# design.net
KiCad netlist of a schematic drawn in Altium Designer
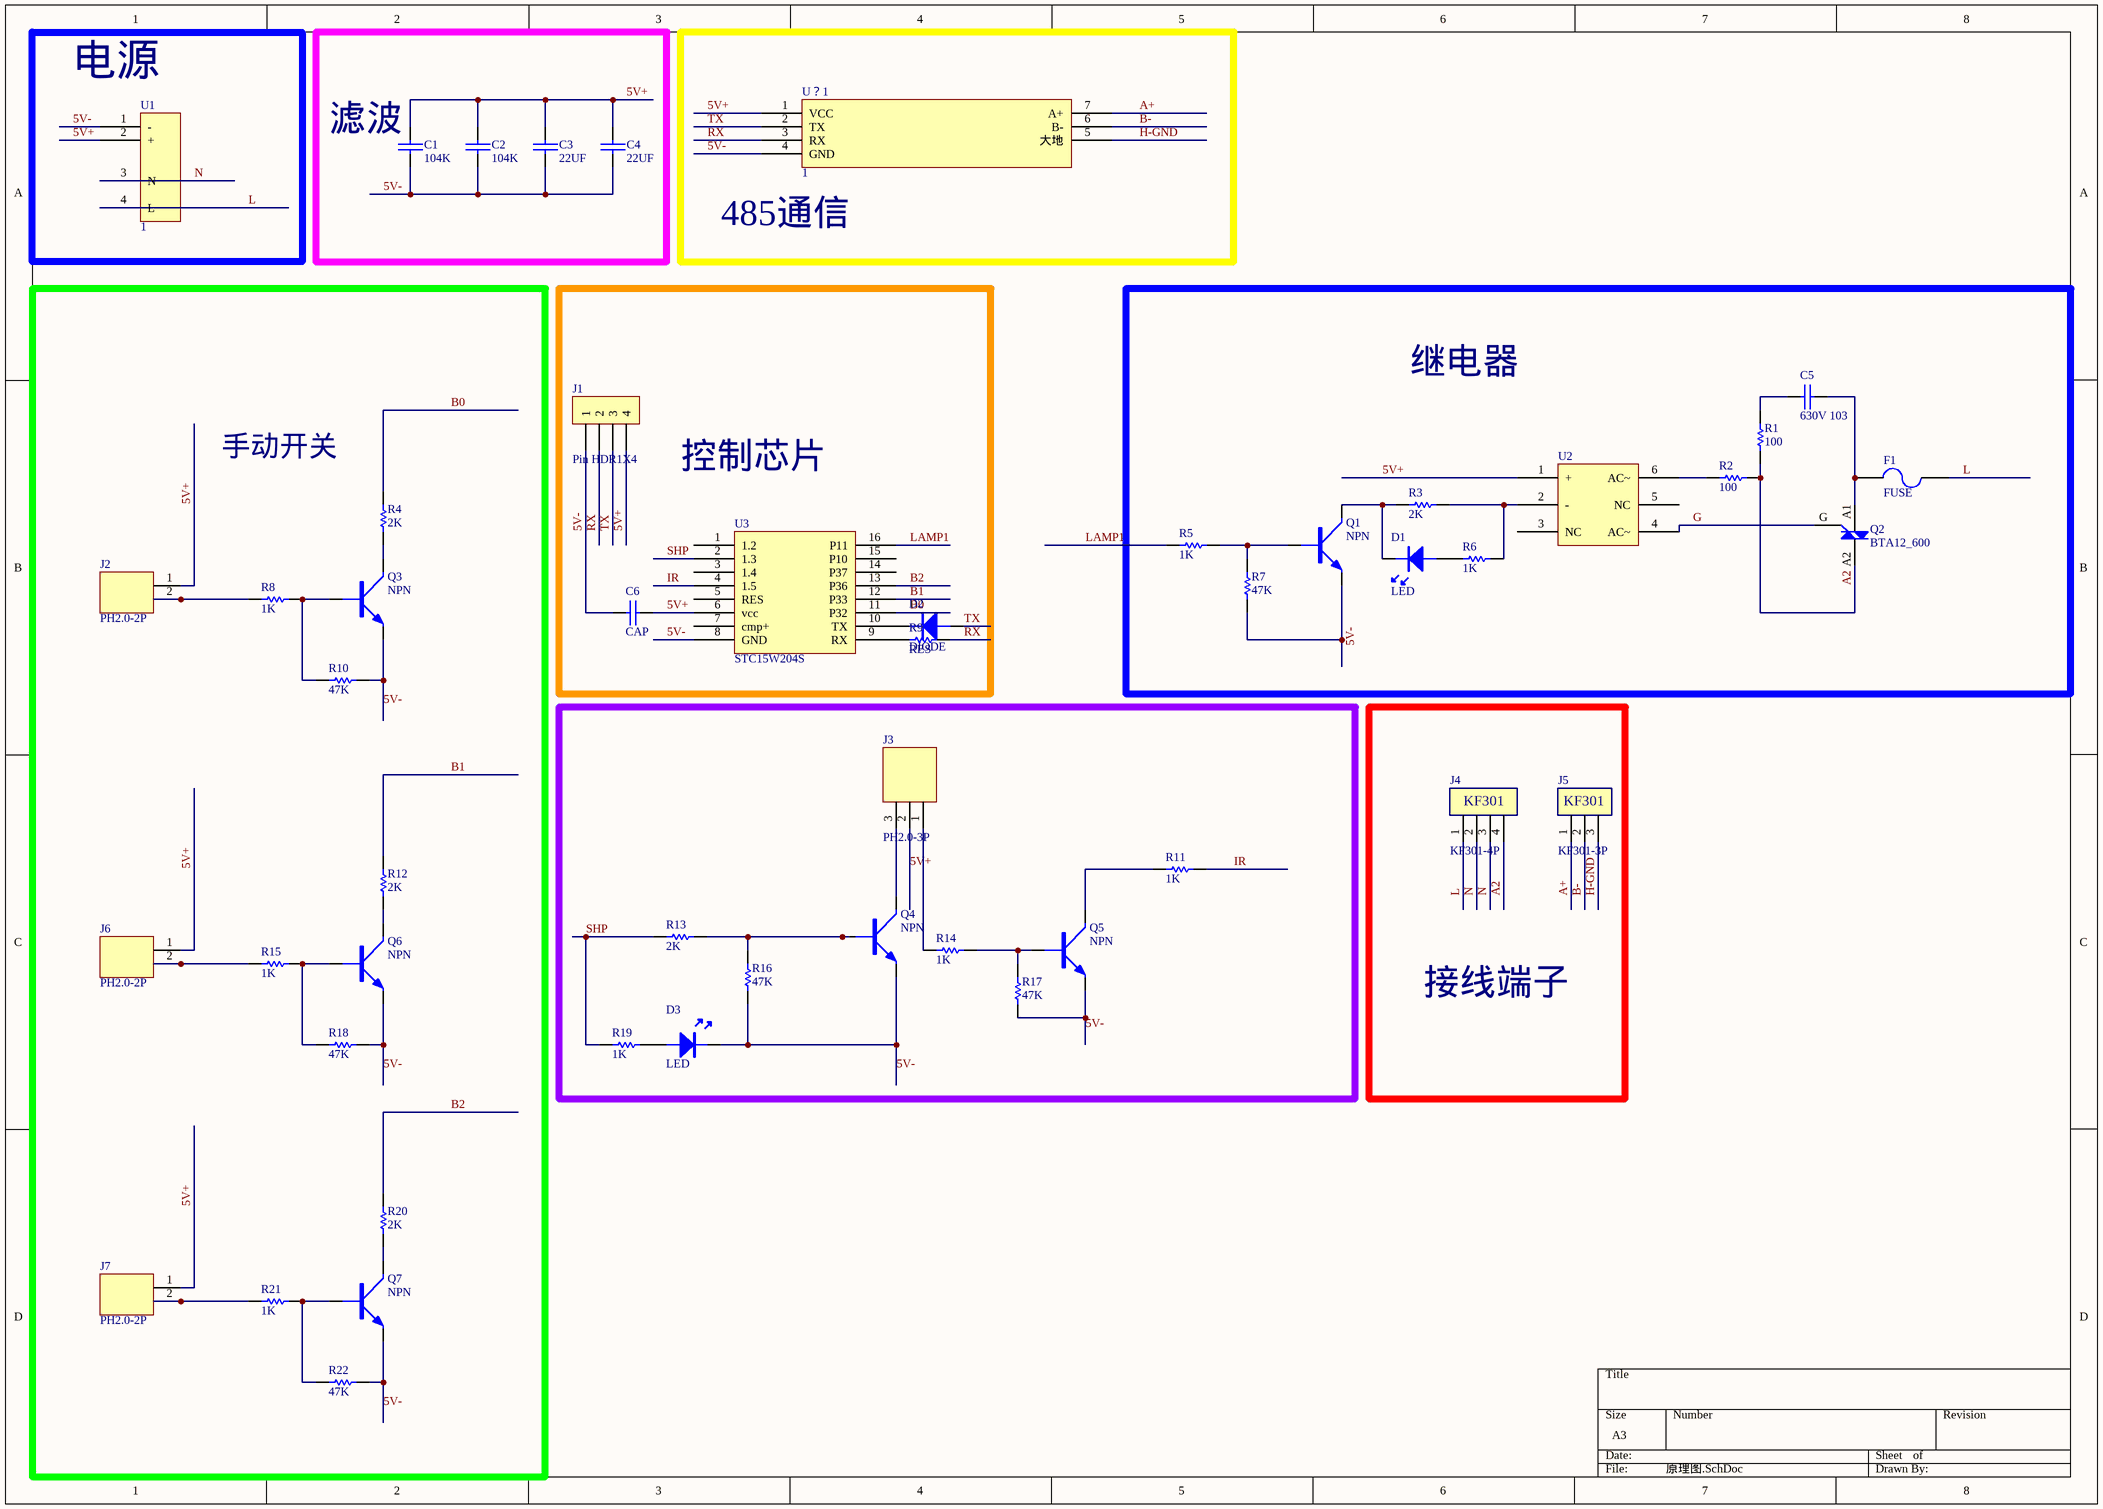
[diagram p0: 原理图.SchDoc]

(export (version "E")
  (design (tool "Eeschema 10.0.6"))
  (components
    (comp (ref "C1")
      (value "104K")
      (footprint "0603C")
      (description "无极性电容")
      (libsource (lib "电容") (part "CAP"))
    )
    (comp (ref "C2")
      (value "104K")
      (footprint "0603C")
      (description "无极性电容")
      (libsource (lib "电容") (part "CAP"))
    )
    (comp (ref "C3")
      (value "22UF")
      (footprint "0603C")
      (description "无极性电容")
      (libsource (lib "电容") (part "CAP"))
    )
    (comp (ref "C4")
      (value "22UF")
      (footprint "0603C")
      (description "无极性电容")
      (libsource (lib "电容") (part "CAP"))
    )
    (comp (ref "C5")
      (value "630V 103")
      (footprint "RAD-0.3")
      (description "无极性电容")
      (libsource (lib "电容") (part "CAP"))
    )
    (comp (ref "C6")
      (value "CAP")
      (footprint "0603C")
      (description "无极性电容")
      (libsource (lib "电容") (part "CAP"))
    )
    (comp (ref "D1") (value "LED") (footprint "LED-0603G") (libsource (lib "LED") (part "LED")))
    (comp (ref "D2")
      (value "DIODE")
      (footprint "SOD-523")
      (description "普通二极管")
      (libsource (lib "二极管") (part "DIODE"))
    )
    (comp (ref "D3") (value "LED") (footprint "LED-0603G") (libsource (lib "LED") (part "LED")))
    (comp (ref "F1") (value "FUSE") (footprint "FUSE-4x16") (libsource (lib "保险丝") (part "FUSE")))
    (comp (ref "J1") (value "Pin HDR1X4") (footprint "MHDR1X4") (libsource (lib "排针") (part "Pin HDR1X4")))
    (comp (ref "J2") (value "PH2.0-2P") (footprint "PH2.0-2P") (libsource (lib "PH") (part "PH2.0-2P")))
    (comp (ref "J3") (value "PH2.0-3P") (footprint "PH2.0-3P") (libsource (lib "PH") (part "PH2.0-3P")))
    (comp (ref "J4")
      (value "KF301-4P")
      (footprint "KF301-5.0-4P")
      (libsource (lib "KF301") (part "KF301-4P"))
    )
    (comp (ref "J5")
      (value "KF301-3P")
      (footprint "KF301-5.0-3P")
      (libsource (lib "KF301") (part "KF301-3P"))
    )
    (comp (ref "J6") (value "PH2.0-2P") (footprint "PH2.0-2P") (libsource (lib "PH") (part "PH2.0-2P")))
    (comp (ref "J7") (value "PH2.0-2P") (footprint "PH2.0-2P") (libsource (lib "PH") (part "PH2.0-2P")))
    (comp (ref "Q1")
      (value "NPN")
      (footprint "SOT-23")
      (description "NPN三极管")
      (libsource (lib "三极管") (part "NPN"))
    )
    (comp (ref "Q2")
      (value "BTA12_600")
      (footprint "TO220A")
      (description "双向可控硅")
      (libsource (lib "可控硅") (part "BTA12_600"))
    )
    (comp (ref "Q3")
      (value "NPN")
      (footprint "SOT-23")
      (description "NPN三极管")
      (libsource (lib "三极管") (part "NPN"))
    )
    (comp (ref "Q4")
      (value "NPN")
      (footprint "SOT-23")
      (description "NPN三极管")
      (libsource (lib "三极管") (part "NPN"))
    )
    (comp (ref "Q5")
      (value "NPN")
      (footprint "SOT-23")
      (description "NPN三极管")
      (libsource (lib "三极管") (part "NPN"))
    )
    (comp (ref "Q6")
      (value "NPN")
      (footprint "SOT-23")
      (description "NPN三极管")
      (libsource (lib "三极管") (part "NPN"))
    )
    (comp (ref "Q7")
      (value "NPN")
      (footprint "SOT-23")
      (description "NPN三极管")
      (libsource (lib "三极管") (part "NPN"))
    )
    (comp (ref "R1") (value "100") (footprint "AXIAL0.4") (libsource (lib "电阻") (part "RES")))
    (comp (ref "R2") (value "100") (footprint "AXIAL0.4") (libsource (lib "电阻") (part "RES")))
    (comp (ref "R3") (value "2K") (footprint "0402R") (libsource (lib "电阻") (part "RES")))
    (comp (ref "R4") (value "2K") (footprint "0402R") (libsource (lib "电阻") (part "RES")))
    (comp (ref "R5") (value "1K") (footprint "0402R") (libsource (lib "电阻") (part "RES")))
    (comp (ref "R6") (value "1K") (footprint "0402R") (libsource (lib "电阻") (part "RES")))
    (comp (ref "R7") (value "47K") (footprint "0402R") (libsource (lib "电阻") (part "RES")))
    (comp (ref "R8") (value "1K") (footprint "0402R") (libsource (lib "电阻") (part "RES")))
    (comp (ref "R9") (value "RES") (footprint "0402R") (libsource (lib "电阻") (part "RES")))
    (comp (ref "R10") (value "47K") (footprint "0402R") (libsource (lib "电阻") (part "RES")))
    (comp (ref "R11") (value "1K") (footprint "0402R") (libsource (lib "电阻") (part "RES")))
    (comp (ref "R12") (value "2K") (footprint "0402R") (libsource (lib "电阻") (part "RES")))
    (comp (ref "R13") (value "2K") (footprint "0402R") (libsource (lib "电阻") (part "RES")))
    (comp (ref "R14") (value "1K") (footprint "0402R") (libsource (lib "电阻") (part "RES")))
    (comp (ref "R15") (value "1K") (footprint "0402R") (libsource (lib "电阻") (part "RES")))
    (comp (ref "R16") (value "47K") (footprint "0402R") (libsource (lib "电阻") (part "RES")))
    (comp (ref "R17") (value "47K") (footprint "0402R") (libsource (lib "电阻") (part "RES")))
    (comp (ref "R18") (value "47K") (footprint "0402R") (libsource (lib "电阻") (part "RES")))
    (comp (ref "R19") (value "1K") (footprint "0402R") (libsource (lib "电阻") (part "RES")))
    (comp (ref "R20") (value "2K") (footprint "0402R") (libsource (lib "电阻") (part "RES")))
    (comp (ref "R21") (value "1K") (footprint "0402R") (libsource (lib "电阻") (part "RES")))
    (comp (ref "R22") (value "47K") (footprint "0402R") (libsource (lib "电阻") (part "RES")))
    (comp (ref "U1")
      (value "1")
      (footprint "开关电路")
      (libsource (lib "5v700MA_SWITCH_POWER") (part "220TO5V-power"))
    )
    (comp (ref "U2") (value "~") (footprint "DIP6") (libsource (lib "MOC3052") (part "Component_1")))
    (comp (ref "U3")
      (value "STC15W204S")
      (footprint "SOP16")
      (libsource (lib "STC15W204S") (part "STC15W204S"))
    )
    (comp (ref "U？1") (value "1") (footprint "485通信模块") (libsource (lib "485模块") (part "485通信模块")))
  )
  (nets
    (net (code "1") (name "/5V+") (class "Default")
      (node (ref "C1") (pin "2") (pinfunction "2_2") (pintype "passive"))
      (node (ref "C2") (pin "2") (pinfunction "2_2") (pintype "passive"))
      (node (ref "C3") (pin "2") (pinfunction "2_2") (pintype "passive"))
      (node (ref "C4") (pin "2") (pinfunction "2_2") (pintype "passive"))
      (node (ref "C6") (pin "2") (pinfunction "2_2") (pintype "passive"))
      (node (ref "J1") (pin "4") (pinfunction "4_4") (pintype "passive"))
      (node (ref "J2") (pin "1") (pinfunction "1_1") (pintype "passive"))
      (node (ref "J3") (pin "2") (pinfunction "2_2") (pintype "passive"))
      (node (ref "J6") (pin "1") (pinfunction "1_1") (pintype "passive"))
      (node (ref "J7") (pin "1") (pinfunction "1_1") (pintype "passive"))
      (node (ref "U1") (pin "2") (pinfunction "+_2") (pintype "passive"))
      (node (ref "U2") (pin "1") (pinfunction "+_1") (pintype "passive"))
      (node (ref "U3") (pin "6") (pinfunction "vcc_6") (pintype "passive"))
      (node (ref "U？1") (pin "1") (pinfunction "VCC_1") (pintype "passive"))
    )
    (net (code "2") (name "/5V-") (class "Default")
      (node (ref "C1") (pin "1") (pinfunction "1_1") (pintype "passive"))
      (node (ref "C2") (pin "1") (pinfunction "1_1") (pintype "passive"))
      (node (ref "C3") (pin "1") (pinfunction "1_1") (pintype "passive"))
      (node (ref "C4") (pin "1") (pinfunction "1_1") (pintype "passive"))
      (node (ref "C6") (pin "1") (pinfunction "1_1") (pintype "passive"))
      (node (ref "D3") (pin "K") (pinfunction "K_K") (pintype "passive"))
      (node (ref "J1") (pin "1") (pinfunction "1_1") (pintype "passive"))
      (node (ref "Q1") (pin "E") (pinfunction "E_E") (pintype "passive"))
      (node (ref "Q3") (pin "E") (pinfunction "E_E") (pintype "passive"))
      (node (ref "Q4") (pin "E") (pinfunction "E_E") (pintype "passive"))
      (node (ref "Q5") (pin "E") (pinfunction "E_E") (pintype "passive"))
      (node (ref "Q6") (pin "E") (pinfunction "E_E") (pintype "passive"))
      (node (ref "Q7") (pin "E") (pinfunction "E_E") (pintype "passive"))
      (node (ref "R10") (pin "2") (pinfunction "2_2") (pintype "passive"))
      (node (ref "R16") (pin "1") (pinfunction "1_1") (pintype "passive"))
      (node (ref "R17") (pin "1") (pinfunction "1_1") (pintype "passive"))
      (node (ref "R18") (pin "2") (pinfunction "2_2") (pintype "passive"))
      (node (ref "R22") (pin "2") (pinfunction "2_2") (pintype "passive"))
      (node (ref "R7") (pin "1") (pinfunction "1_1") (pintype "passive"))
      (node (ref "U1") (pin "1") (pinfunction "-_1") (pintype "passive"))
      (node (ref "U3") (pin "8") (pinfunction "GND_8") (pintype "passive"))
      (node (ref "U？1") (pin "4") (pinfunction "GND_4") (pintype "passive"))
    )
    (net (code "3") (name "/A+") (class "Default")
      (node (ref "J5") (pin "1") (pinfunction "1_1") (pintype "passive"))
      (node (ref "U？1") (pin "7") (pinfunction "A+_7") (pintype "passive"))
    )
    (net (code "4") (name "/A2") (class "Default")
      (node (ref "J4") (pin "4") (pinfunction "4_4") (pintype "passive"))
      (node (ref "Q2") (pin "A2") (pinfunction "A2_A2") (pintype "passive"))
      (node (ref "R1") (pin "1") (pinfunction "1_1") (pintype "passive"))
      (node (ref "R2") (pin "2") (pinfunction "2_2") (pintype "passive"))
    )
    (net (code "5") (name "/B-") (class "Default")
      (node (ref "J5") (pin "2") (pinfunction "2_2") (pintype "passive"))
      (node (ref "U？1") (pin "6") (pinfunction "B-_6") (pintype "passive"))
    )
    (net (code "6") (name "/B0") (class "Default")
      (node (ref "R4") (pin "2") (pinfunction "2_2") (pintype "passive"))
      (node (ref "U3") (pin "11") (pinfunction "P32_11") (pintype "passive"))
    )
    (net (code "7") (name "/B1") (class "Default")
      (node (ref "R12") (pin "2") (pinfunction "2_2") (pintype "passive"))
      (node (ref "U3") (pin "12") (pinfunction "P33_12") (pintype "passive"))
    )
    (net (code "8") (name "/B2") (class "Default")
      (node (ref "R20") (pin "2") (pinfunction "2_2") (pintype "passive"))
      (node (ref "U3") (pin "13") (pinfunction "P36_13") (pintype "passive"))
    )
    (net (code "9") (name "/G") (class "Default")
      (node (ref "Q2") (pin "G") (pinfunction "G_G") (pintype "passive"))
      (node (ref "U2") (pin "4") (pinfunction "AC~_4") (pintype "passive"))
    )
    (net (code "10") (name "/H-GND") (class "Default")
      (node (ref "J5") (pin "3") (pinfunction "3_3") (pintype "passive"))
      (node (ref "U？1") (pin "5") (pinfunction "大地_5") (pintype "passive"))
    )
    (net (code "11") (name "/IR") (class "Default")
      (node (ref "R11") (pin "2") (pinfunction "2_2") (pintype "passive"))
      (node (ref "U3") (pin "4") (pinfunction "1.5_4") (pintype "passive"))
    )
    (net (code "12") (name "/L") (class "Default")
      (node (ref "F1") (pin "2") (pinfunction "2_2") (pintype "passive"))
      (node (ref "J4") (pin "1") (pinfunction "1_1") (pintype "passive"))
      (node (ref "U1") (pin "4") (pinfunction "L_4") (pintype "passive"))
    )
    (net (code "13") (name "/LAMP1") (class "Default")
      (node (ref "R5") (pin "1") (pinfunction "1_1") (pintype "passive"))
      (node (ref "U3") (pin "16") (pinfunction "P11_16") (pintype "passive"))
    )
    (net (code "14") (name "/N") (class "Default")
      (node (ref "J4") (pin "2") (pinfunction "2_2") (pintype "passive"))
      (node (ref "J4") (pin "3") (pinfunction "3_3") (pintype "passive"))
      (node (ref "U1") (pin "3") (pinfunction "N_3") (pintype "passive"))
    )
    (net (code "15") (name "/RX") (class "Default")
      (node (ref "J1") (pin "2") (pinfunction "2_2") (pintype "passive"))
      (node (ref "R9") (pin "2") (pinfunction "2_2") (pintype "passive"))
      (node (ref "U？1") (pin "3") (pinfunction "RX_3") (pintype "passive"))
    )
    (net (code "16") (name "/SHP") (class "Default")
      (node (ref "R13") (pin "1") (pinfunction "1_1") (pintype "passive"))
      (node (ref "R19") (pin "1") (pinfunction "1_1") (pintype "passive"))
      (node (ref "U3") (pin "2") (pinfunction "1.3_2") (pintype "passive"))
    )
    (net (code "17") (name "/TX") (class "Default")
      (node (ref "D2") (pin "A") (pinfunction "A_A") (pintype "passive"))
      (node (ref "J1") (pin "3") (pinfunction "3_3") (pintype "passive"))
      (node (ref "U？1") (pin "2") (pinfunction "TX_2") (pintype "passive"))
    )
    (net (code "18") (name "Net-(C5-Pad1)") (class "Default")
      (node (ref "C5") (pin "1") (pinfunction "1_1") (pintype "passive"))
      (node (ref "R1") (pin "2") (pinfunction "2_2") (pintype "passive"))
    )
    (net (code "19") (name "Net-(C5-Pad2)") (class "Default")
      (node (ref "C5") (pin "2") (pinfunction "2_2") (pintype "passive"))
      (node (ref "F1") (pin "1") (pinfunction "1_1") (pintype "passive"))
      (node (ref "Q2") (pin "A1") (pinfunction "A1_A1") (pintype "passive"))
    )
    (net (code "20") (name "Net-(D1-PadA)") (class "Default")
      (node (ref "D1") (pin "A") (pinfunction "A_A") (pintype "passive"))
      (node (ref "R6") (pin "1") (pinfunction "1_1") (pintype "passive"))
    )
    (net (code "21") (name "Net-(D1-PadK)") (class "Default")
      (node (ref "D1") (pin "K") (pinfunction "K_K") (pintype "passive"))
      (node (ref "Q1") (pin "C") (pinfunction "C_C") (pintype "passive"))
      (node (ref "R3") (pin "1") (pinfunction "1_1") (pintype "passive"))
    )
    (net (code "22") (name "Net-(D3-PadA)") (class "Default")
      (node (ref "D3") (pin "A") (pinfunction "A_A") (pintype "passive"))
      (node (ref "R19") (pin "2") (pinfunction "2_2") (pintype "passive"))
    )
    (net (code "23") (name "Net-(J2-Pad2)") (class "Default")
      (node (ref "J2") (pin "2") (pinfunction "2_2") (pintype "passive"))
      (node (ref "R8") (pin "1") (pinfunction "1_1") (pintype "passive"))
    )
    (net (code "24") (name "Net-(J3-Pad1)") (class "Default")
      (node (ref "J3") (pin "1") (pinfunction "1_1") (pintype "passive"))
      (node (ref "R14") (pin "2") (pinfunction "2_2") (pintype "passive"))
    )
    (net (code "25") (name "Net-(J3-Pad3)") (class "Default")
      (node (ref "J3") (pin "3") (pinfunction "3_3") (pintype "passive"))
      (node (ref "Q4") (pin "C") (pinfunction "C_C") (pintype "passive"))
    )
    (net (code "26") (name "Net-(J6-Pad2)") (class "Default")
      (node (ref "J6") (pin "2") (pinfunction "2_2") (pintype "passive"))
      (node (ref "R15") (pin "1") (pinfunction "1_1") (pintype "passive"))
    )
    (net (code "27") (name "Net-(J7-Pad2)") (class "Default")
      (node (ref "J7") (pin "2") (pinfunction "2_2") (pintype "passive"))
      (node (ref "R21") (pin "1") (pinfunction "1_1") (pintype "passive"))
    )
    (net (code "28") (name "Net-(Q1-PadB)") (class "Default")
      (node (ref "Q1") (pin "B") (pinfunction "B_B") (pintype "passive"))
      (node (ref "R5") (pin "2") (pinfunction "2_2") (pintype "passive"))
      (node (ref "R7") (pin "2") (pinfunction "2_2") (pintype "passive"))
    )
    (net (code "29") (name "Net-(Q3-PadB)") (class "Default")
      (node (ref "Q3") (pin "B") (pinfunction "B_B") (pintype "passive"))
      (node (ref "R10") (pin "1") (pinfunction "1_1") (pintype "passive"))
      (node (ref "R8") (pin "2") (pinfunction "2_2") (pintype "passive"))
    )
    (net (code "30") (name "Net-(Q3-PadC)") (class "Default")
      (node (ref "Q3") (pin "C") (pinfunction "C_C") (pintype "passive"))
      (node (ref "R4") (pin "1") (pinfunction "1_1") (pintype "passive"))
    )
    (net (code "31") (name "Net-(Q4-PadB)") (class "Default")
      (node (ref "Q4") (pin "B") (pinfunction "B_B") (pintype "passive"))
      (node (ref "R13") (pin "2") (pinfunction "2_2") (pintype "passive"))
      (node (ref "R16") (pin "2") (pinfunction "2_2") (pintype "passive"))
    )
    (net (code "32") (name "Net-(Q5-PadB)") (class "Default")
      (node (ref "Q5") (pin "B") (pinfunction "B_B") (pintype "passive"))
      (node (ref "R14") (pin "1") (pinfunction "1_1") (pintype "passive"))
      (node (ref "R17") (pin "2") (pinfunction "2_2") (pintype "passive"))
    )
    (net (code "33") (name "Net-(Q5-PadC)") (class "Default")
      (node (ref "Q5") (pin "C") (pinfunction "C_C") (pintype "passive"))
      (node (ref "R11") (pin "1") (pinfunction "1_1") (pintype "passive"))
    )
    (net (code "34") (name "Net-(Q6-PadB)") (class "Default")
      (node (ref "Q6") (pin "B") (pinfunction "B_B") (pintype "passive"))
      (node (ref "R15") (pin "2") (pinfunction "2_2") (pintype "passive"))
      (node (ref "R18") (pin "1") (pinfunction "1_1") (pintype "passive"))
    )
    (net (code "35") (name "Net-(Q6-PadC)") (class "Default")
      (node (ref "Q6") (pin "C") (pinfunction "C_C") (pintype "passive"))
      (node (ref "R12") (pin "1") (pinfunction "1_1") (pintype "passive"))
    )
    (net (code "36") (name "Net-(Q7-PadB)") (class "Default")
      (node (ref "Q7") (pin "B") (pinfunction "B_B") (pintype "passive"))
      (node (ref "R21") (pin "2") (pinfunction "2_2") (pintype "passive"))
      (node (ref "R22") (pin "1") (pinfunction "1_1") (pintype "passive"))
    )
    (net (code "37") (name "Net-(Q7-PadC)") (class "Default")
      (node (ref "Q7") (pin "C") (pinfunction "C_C") (pintype "passive"))
      (node (ref "R20") (pin "1") (pinfunction "1_1") (pintype "passive"))
    )
    (net (code "38") (name "Net-(R2-Pad1)") (class "Default")
      (node (ref "R2") (pin "1") (pinfunction "1_1") (pintype "passive"))
      (node (ref "U2") (pin "6") (pinfunction "AC~_6") (pintype "passive"))
    )
    (net (code "39") (name "Net-(U2--)") (class "Default")
      (node (ref "R3") (pin "2") (pinfunction "2_2") (pintype "passive"))
      (node (ref "R6") (pin "2") (pinfunction "2_2") (pintype "passive"))
      (node (ref "U2") (pin "2") (pinfunction "-_2") (pintype "passive"))
    )
    (net (code "40") (name "Net-(U3-RX)") (class "Default")
      (node (ref "R9") (pin "1") (pinfunction "1_1") (pintype "passive"))
      (node (ref "U3") (pin "9") (pinfunction "RX_9") (pintype "passive"))
    )
    (net (code "41") (name "Net-(U3-TX)") (class "Default")
      (node (ref "D2") (pin "K") (pinfunction "K_K") (pintype "passive"))
      (node (ref "U3") (pin "10") (pinfunction "TX_10") (pintype "passive"))
    )
    (net (code "42") (name "unconnected-(U2-NC-Pad3)") (class "Default")
      (node (ref "U2") (pin "3") (pinfunction "NC_3") (pintype "passive"))
    )
    (net (code "43") (name "unconnected-(U2-NC-Pad5)") (class "Default")
      (node (ref "U2") (pin "5") (pinfunction "NC_5") (pintype "passive"))
    )
    (net (code "44") (name "unconnected-(U3-1.2-Pad1)") (class "Default")
      (node (ref "U3") (pin "1") (pinfunction "1.2_1") (pintype "passive"))
    )
    (net (code "45") (name "unconnected-(U3-1.4-Pad3)") (class "Default")
      (node (ref "U3") (pin "3") (pinfunction "1.4_3") (pintype "passive"))
    )
    (net (code "46") (name "unconnected-(U3-P10-Pad15)") (class "Default")
      (node (ref "U3") (pin "15") (pinfunction "P10_15") (pintype "passive"))
    )
    (net (code "47") (name "unconnected-(U3-P37-Pad14)") (class "Default")
      (node (ref "U3") (pin "14") (pinfunction "P37_14") (pintype "passive"))
    )
    (net (code "48") (name "unconnected-(U3-RES-Pad5)") (class "Default")
      (node (ref "U3") (pin "5") (pinfunction "RES_5") (pintype "passive"))
    )
    (net (code "49") (name "unconnected-(U3-cmp+-Pad7)") (class "Default")
      (node (ref "U3") (pin "7") (pinfunction "cmp+_7") (pintype "passive"))
    )
  )
)
